# 7_PowerManagement.net
KiCad netlist of a schematic drawn in Altium Designer
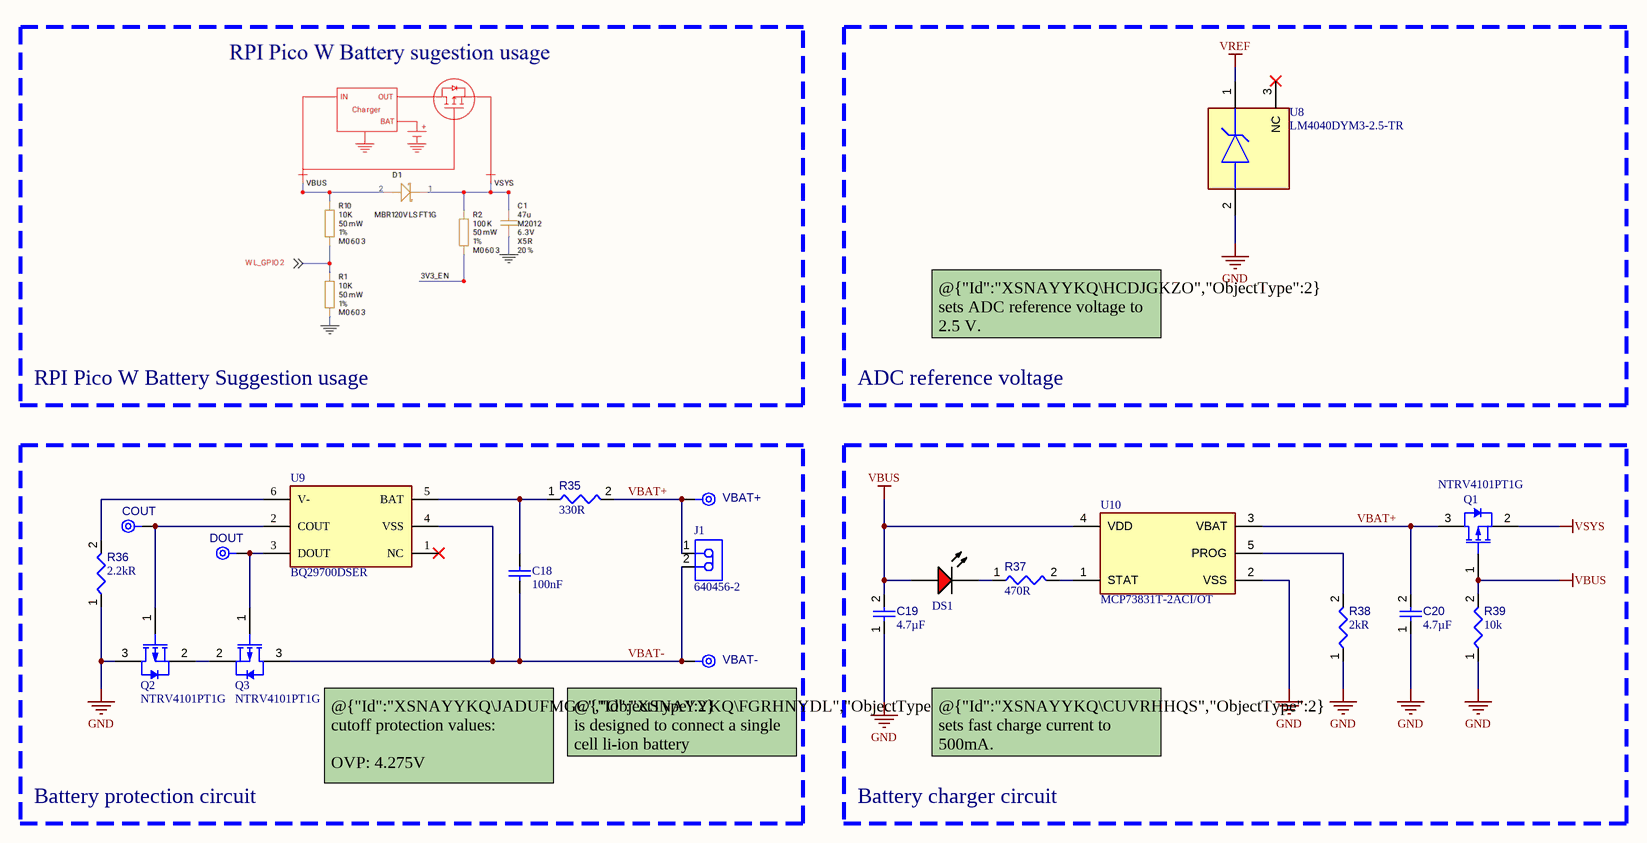
[diagram p0: [7] PowerManagement.SchDoc]

(export (version "E")
  (design (tool "Eeschema 10.0.6"))
  (components
    (comp (ref "C18")
      (value "100nF")
      (footprint "CAPC0603(1608)100_L")
      (description "Multilayer Ceramic Capacitor, 0.1 uF, 16 V, ± 20%, X7R, 0603 [1608 Metric]")
      (fields (field (name "TOLERANCE") "20%") (field (name "Comment") "VJ0603Y104MXJCW1BC"))
      (libsource (lib "UFCG - Universidade Federal de Campina Grande") (part "CAP"))
    )
    (comp (ref "C19")
      (value "4.7µF")
      (footprint "CAPC0603(1608)100_L")
      (description "Chip Capacitor, 4.7µF +/-20%, 10V, 0603, Thickness 1 mm")
      (fields (field (name "TOLERANCE") "10%") (field (name "Comment") "Capacitor 4.7µF +/-20% 10V 0603"))
      (libsource (lib "UFCG - Universidade Federal de Campina Grande") (part "CAP-NP-2"))
    )
    (comp (ref "C20")
      (value "4.7µF")
      (footprint "CAPC0603(1608)100_L")
      (description "Chip Capacitor, 4.7µF +/-20%, 10V, 0603, Thickness 1 mm")
      (fields (field (name "TOLERANCE") "10%") (field (name "Comment") "Capacitor 4.7µF +/-20% 10V 0603"))
      (libsource (lib "UFCG - Universidade Federal de Campina Grande") (part "CAP-NP-2"))
    )
    (comp (ref "COUT")
      (value "TPAD6R")
      (footprint "TP06R")
      (description "0.6mm round")
      (libsource (lib "PCEIOT") (part "CMP-00028-00002-2"))
    )
    (comp (ref "DOUT")
      (value "TPAD6R")
      (footprint "TP06R")
      (description "0.6mm round")
      (libsource (lib "PCEIOT") (part "CMP-00028-00002-2"))
    )
    (comp (ref "DS1")
      (value "19-217/R6C-AL1M2VY/3T")
      (footprint "EVRL-0603-2_V")
      (description "Chip LED, Red, 5 V, 25 mA, -40 to 85 degC, 2-Pin SMD (0603), RoHS, Tape and Reel")
      (fields (field (name "MANUFACTURER") "Everlight Electronics"))
      (libsource (lib "UFCG - Universidade Federal de Campina Grande") (part "LED-RED-AK-2"))
    )
    (comp (ref "J1")
      (value "640456-2")
      (footprint "TECO-640456-2_V")
      (description "Connector 250V AC/DC 5A 2P 1 Row PCB - Vertical Mounting Polyester White")
      (libsource (lib "UFCG - Universidade Federal de Campina Grande") (part "CN-2P-F-QF2"))
    )
    (comp (ref "Q1")
      (value "NTRV4101PT1G")
      (footprint "ONSC-SOT-23-3-318-08_V")
      (description "NTRV4101PT1G P-channel MOSFET Transistor; 1.7 A; 20 V; 3-Pin SOT-23")
      (libsource (lib "UFCG - Universidade Federal de Campina Grande") (part "ONSC-PMOS-G1S2D3-3_D"))
    )
    (comp (ref "Q2")
      (value "NTRV4101PT1G")
      (footprint "ONSC-SOT-23-3-318-08_V")
      (description "NTRV4101PT1G P-channel MOSFET Transistor; 1.7 A; 20 V; 3-Pin SOT-23")
      (libsource (lib "UFCG - Universidade Federal de Campina Grande") (part "ONSC-PMOS-G1S2D3-3_D"))
    )
    (comp (ref "Q3")
      (value "NTRV4101PT1G")
      (footprint "ONSC-SOT-23-3-318-08_V")
      (description "NTRV4101PT1G P-channel MOSFET Transistor; 1.7 A; 20 V; 3-Pin SOT-23")
      (libsource (lib "UFCG - Universidade Federal de Campina Grande") (part "ONSC-PMOS-G1S2D3-3_D"))
    )
    (comp (ref "R35")
      (value "330R")
      (footprint "RESC0603(1608)_L")
      (description "SMD Chip Resistor, 330 Ohm, ± 1%, 100 mW, 0603 [1608 Metric], Thick Film, Precision")
      (fields (field (name "TOLERANCE") "1%") (field (name "Comment") "ERJ-3EKF3300V"))
      (libsource (lib "UFCG - Universidade Federal de Campina Grande") (part "RES-2"))
    )
    (comp (ref "R36")
      (value "2.2kR")
      (footprint "RESC0603(1608)_L")
      (description "SMD Chip Resistor, 2.2 kOhm, ± 1%, 100 mW, 0603 [1608 Metric], Thick Film, General Purpose")
      (fields (field (name "TOLERANCE") "1%") (field (name "Comment") "CRCW06032K20FKEA"))
      (libsource (lib "UFCG - Universidade Federal de Campina Grande") (part "RES-2"))
    )
    (comp (ref "R37")
      (value "470R")
      (footprint "RESC0603(1608)_L")
      (description "Res Thick Film 0603 470 Ohm 5% 0.1W(1/10W) ±200ppm/°C Pad SMD Automotive T/R")
      (fields (field (name "TOLERANCE") "5%") (field (name "Comment") "CRCW0603470RJNEA"))
      (libsource (lib "UFCG - Universidade Federal de Campina Grande") (part "RES-2"))
    )
    (comp (ref "R38")
      (value "2kR")
      (footprint "RESC0603(1608)_L")
      (description "SMD Chip Resistor, 2 kOhm, ï¿½ 1%, 100 mW, 0603 [1608 Metric], Thick Film, Precision")
      (fields (field (name "TOLERANCE") "1%") (field (name "Comment") "ERJ-3EKF2001V"))
      (libsource (lib "UFCG - Universidade Federal de Campina Grande") (part "RES-2"))
    )
    (comp (ref "R39")
      (value "10k")
      (footprint "RESC0603(1608)_L")
      (description "Chip Resistor, 10 KOhm, +/- 1%, 01 W, -55 to 155 degC, 0603 (1608 Metric)")
      (fields (field (name "POWER") "100mW") (field (name "TOLERANCE") "1%"))
      (libsource (lib "UFCG - Universidade Federal de Campina Grande") (part "RES-2"))
    )
    (comp (ref "U8")
      (value "LM4040DYM3-2.5-TR")
      (footprint "FP-SOT23-3LD-PL-1-IPC_A")
      (description "LM4040 Series 2.5 V ±1 % Precision Micropower Shunt Voltage Reference - SOT-23")
      (fields (field (name "TOLERANCE") "1%"))
      (libsource (lib "UFCG - Universidade Federal de Campina Grande") (part "91f0ca7be5727739b22823fb575e884"))
    )
    (comp (ref "U9")
      (value "BQ29700DSER")
      (footprint "FP-DSE0006A-MFG")
      (description "Li-Ion/Li Polymer Advanced Single-Cell Battery Protector IC Family 6-WSON -40 to 85")
      (libsource (lib "UFCG - Universidade Federal de Campina Grande") (part "cb1a035e2e9bf15fad579f9d3aca51e"))
    )
    (comp (ref "U10")
      (value "MCP73831T-2ACI/OT")
      (footprint "FP-C04-091-OT-MFG")
      (description "MCP73831 Series Single-Cell Li-Ion/Li-Polymer Battery Charge Controller SOT-23-5")
      (libsource (lib "UFCG - Universidade Federal de Campina Grande") (part "61f5a3bb3429d9e0caadea342aa3b19"))
    )
    (comp (ref "VBAT+")
      (value "TPAD6R")
      (footprint "TP06R")
      (description "0.6mm round")
      (libsource (lib "PCEIOT") (part "CMP-00028-00002-2"))
    )
    (comp (ref "VBAT-")
      (value "TPAD6R")
      (footprint "TP06R")
      (description "0.6mm round")
      (libsource (lib "PCEIOT") (part "CMP-00028-00002-2"))
    )
  )
  (nets
    (net (code "1") (name "/VBAT+") (class "Default")
      (node (ref "C20") (pin "2") (pinfunction "2_2") (pintype "passive"))
      (node (ref "J1") (pin "1") (pinfunction "1_1") (pintype "passive"))
      (node (ref "Q1") (pin "3") (pinfunction "D_3") (pintype "passive"))
      (node (ref "R35") (pin "2") (pinfunction "2_2") (pintype "passive"))
      (node (ref "U10") (pin "3") (pinfunction "VBAT_3") (pintype "power_in"))
      (node (ref "VBAT+") (pin "1") (pinfunction "TP_1") (pintype "passive"))
    )
    (net (code "2") (name "/VBAT-") (class "Default")
      (node (ref "C18") (pin "1") (pinfunction "1_1") (pintype "passive"))
      (node (ref "J1") (pin "2") (pinfunction "2_2") (pintype "passive"))
      (node (ref "Q3") (pin "3") (pinfunction "D_3") (pintype "passive"))
      (node (ref "U9") (pin "4") (pinfunction "VSS_4") (pintype "power_in"))
      (node (ref "VBAT-") (pin "1") (pinfunction "TP_1") (pintype "passive"))
    )
    (net (code "3") (name "GND") (class "Default")
      (node (ref "C19") (pin "1") (pinfunction "1_1") (pintype "passive"))
      (node (ref "C20") (pin "1") (pinfunction "1_1") (pintype "passive"))
      (node (ref "Q2") (pin "3") (pinfunction "D_3") (pintype "passive"))
      (node (ref "R36") (pin "1") (pinfunction "1_1") (pintype "passive"))
      (node (ref "R38") (pin "1") (pinfunction "1_1") (pintype "passive"))
      (node (ref "R39") (pin "1") (pinfunction "1_1") (pintype "passive"))
      (node (ref "U10") (pin "2") (pinfunction "VSS_2") (pintype "power_in"))
      (node (ref "U8") (pin "2") (pinfunction "-_2") (pintype "passive"))
    )
    (net (code "4") (name "Net-(COUT-TP)") (class "Default")
      (node (ref "COUT") (pin "1") (pinfunction "TP_1") (pintype "passive"))
      (node (ref "Q2") (pin "1") (pinfunction "G_1") (pintype "passive"))
      (node (ref "U9") (pin "2") (pinfunction "COUT_2") (pintype "passive"))
    )
    (net (code "5") (name "Net-(DOUT-TP)") (class "Default")
      (node (ref "DOUT") (pin "1") (pinfunction "TP_1") (pintype "passive"))
      (node (ref "Q3") (pin "1") (pinfunction "G_1") (pintype "passive"))
      (node (ref "U9") (pin "3") (pinfunction "DOUT_3") (pintype "passive"))
    )
    (net (code "6") (name "Net-(DS1-K)") (class "Default")
      (node (ref "DS1") (pin "2") (pinfunction "K_2") (pintype "passive"))
      (node (ref "R37") (pin "1") (pinfunction "1_1") (pintype "passive"))
    )
    (net (code "7") (name "Net-(Q2-S)") (class "Default")
      (node (ref "Q2") (pin "2") (pinfunction "S_2") (pintype "passive"))
      (node (ref "Q3") (pin "2") (pinfunction "S_2") (pintype "passive"))
    )
    (net (code "8") (name "Net-(U9-BAT)") (class "Default")
      (node (ref "C18") (pin "2") (pinfunction "2_2") (pintype "passive"))
      (node (ref "R35") (pin "1") (pinfunction "1_1") (pintype "passive"))
      (node (ref "U9") (pin "5") (pinfunction "BAT_5") (pintype "power_in"))
    )
    (net (code "9") (name "Net-(U9-V-)") (class "Default")
      (node (ref "R36") (pin "2") (pinfunction "2_2") (pintype "passive"))
      (node (ref "U9") (pin "6") (pinfunction "V-_6") (pintype "passive"))
    )
    (net (code "10") (name "Net-(U10-PROG)") (class "Default")
      (node (ref "R38") (pin "2") (pinfunction "2_2") (pintype "passive"))
      (node (ref "U10") (pin "5") (pinfunction "PROG_5") (pintype "passive"))
    )
    (net (code "11") (name "Net-(U10-STAT)") (class "Default")
      (node (ref "R37") (pin "2") (pinfunction "2_2") (pintype "passive"))
      (node (ref "U10") (pin "1") (pinfunction "STAT_1") (pintype "passive"))
    )
    (net (code "12") (name "VBUS") (class "Default")
      (node (ref "C19") (pin "2") (pinfunction "2_2") (pintype "passive"))
      (node (ref "DS1") (pin "1") (pinfunction "A_1") (pintype "passive"))
      (node (ref "Q1") (pin "1") (pinfunction "G_1") (pintype "passive"))
      (node (ref "R39") (pin "2") (pinfunction "2_2") (pintype "passive"))
      (node (ref "U10") (pin "4") (pinfunction "VDD_4") (pintype "power_in"))
    )
    (net (code "13") (name "VREF") (class "Default")
      (node (ref "U8") (pin "1") (pinfunction "+_1") (pintype "passive"))
    )
    (net (code "14") (name "VSYS") (class "Default")
      (node (ref "Q1") (pin "2") (pinfunction "S_2") (pintype "passive"))
    )
    (net (code "15") (name "unconnected-(U8-NC-Pad3)") (class "Default")
      (node (ref "U8") (pin "3") (pinfunction "NC_3") (pintype "passive+no_connect"))
    )
    (net (code "16") (name "unconnected-(U9-NC-Pad1)") (class "Default")
      (node (ref "U9") (pin "1") (pinfunction "NC_1") (pintype "passive+no_connect"))
    )
  )
)
